# ATX_Power_Supply.net
KiCad netlist of a schematic drawn in EAGLE
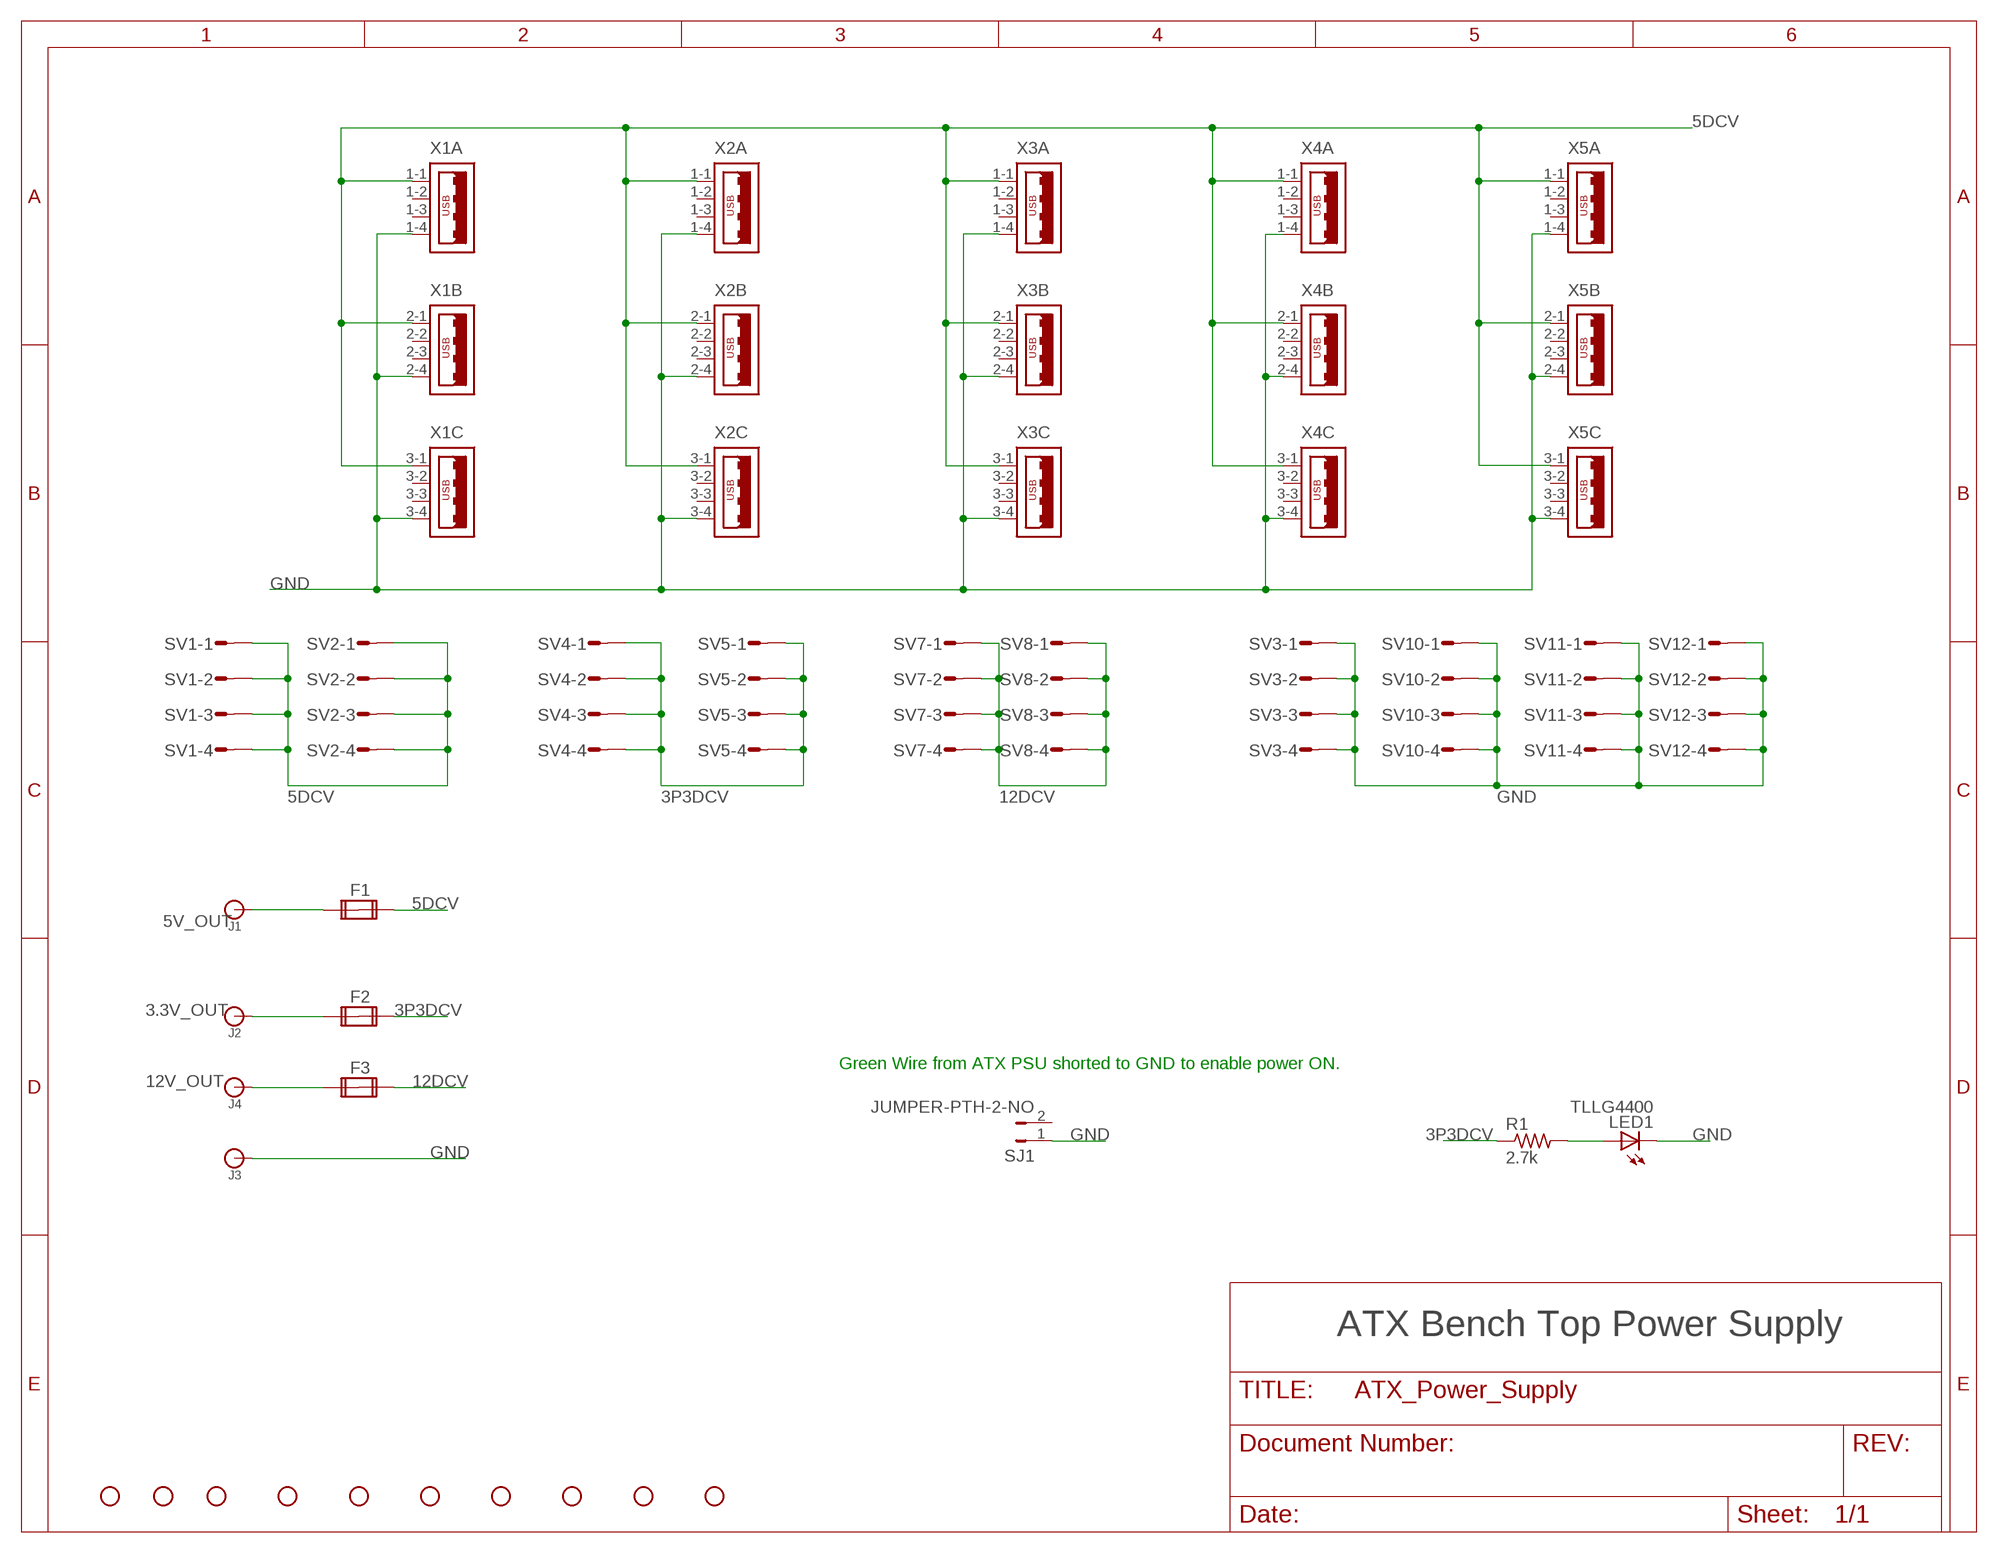
[diagram p0: schematic, sheet 1]

(export (version "E")
  (design (tool "Eeschema 10.0.6"))
  (components
    (comp (ref "F1")
      (value "FUSE2P")
      (footprint "eagle-import:FUSE1")
      (libsource (lib "eagle-import") (part "FUSE2P"))
    )
    (comp (ref "F2")
      (value "FUSE2P")
      (footprint "eagle-import:FUSE1")
      (libsource (lib "eagle-import") (part "FUSE2P"))
    )
    (comp (ref "F3")
      (value "FUSE2P")
      (footprint "eagle-import:FUSE1")
      (libsource (lib "eagle-import") (part "FUSE2P"))
    )
    (comp (ref "J1")
      (value "BANANA_CONN")
      (footprint "eagle-import:BANANA_CONN")
      (libsource (lib "eagle-import") (part "BANANA_CONN"))
    )
    (comp (ref "J2")
      (value "BANANA_CONN")
      (footprint "eagle-import:BANANA_CONN")
      (libsource (lib "eagle-import") (part "BANANA_CONN"))
    )
    (comp (ref "J3")
      (value "BANANA_CONN")
      (footprint "eagle-import:BANANA_CONN")
      (libsource (lib "eagle-import") (part "BANANA_CONN"))
    )
    (comp (ref "J4")
      (value "BANANA_CONN")
      (footprint "eagle-import:BANANA_CONN")
      (libsource (lib "eagle-import") (part "BANANA_CONN"))
    )
    (comp (ref "LED1")
      (value "TLLG4400")
      (footprint "eagle-import:LED3MM")
      (fields (field (name "MF") "VISHAY SEMICONDUCTOR"))
      (libsource (lib "eagle-import") (part "TLLG4400"))
    )
    (comp (ref "R1")
      (value "2.7k")
      (footprint "eagle-import:0204_5")
      (libsource (lib "eagle-import") (part "R-US_0204/5"))
    )
    (comp (ref "SJ1")
      (value "JUMPER-PTH-2-NO")
      (footprint "eagle-import:PTH-JUMPER-2-NO_NO_SILK")
      (libsource (lib "eagle-import") (part "JUMPER-PTH-2-NO"))
    )
    (comp (ref "STANDOFF1")
      (value "STAND-OFF")
      (footprint "eagle-import:STAND-OFF")
      (libsource (lib "eagle-import") (part "STAND-OFF"))
    )
    (comp (ref "STANDOFF2")
      (value "STAND-OFF")
      (footprint "eagle-import:STAND-OFF")
      (libsource (lib "eagle-import") (part "STAND-OFF"))
    )
    (comp (ref "STANDOFF3")
      (value "STAND-OFF")
      (footprint "eagle-import:STAND-OFF")
      (libsource (lib "eagle-import") (part "STAND-OFF"))
    )
    (comp (ref "STANDOFF4")
      (value "STAND-OFF")
      (footprint "eagle-import:STAND-OFF")
      (libsource (lib "eagle-import") (part "STAND-OFF"))
    )
    (comp (ref "STANDOFF5")
      (value "STAND-OFF")
      (footprint "eagle-import:STAND-OFF")
      (libsource (lib "eagle-import") (part "STAND-OFF"))
    )
    (comp (ref "STANDOFF6")
      (value "STAND-OFF")
      (footprint "eagle-import:STAND-OFF")
      (libsource (lib "eagle-import") (part "STAND-OFF"))
    )
    (comp (ref "STANDOFF7")
      (value "STAND-OFF")
      (footprint "eagle-import:STAND-OFF")
      (libsource (lib "eagle-import") (part "STAND-OFF"))
    )
    (comp (ref "STANDOFF8")
      (value "STAND-OFF")
      (footprint "eagle-import:STAND-OFF")
      (libsource (lib "eagle-import") (part "STAND-OFF"))
    )
    (comp (ref "STANDOFF9")
      (value "STAND-OFF")
      (footprint "eagle-import:STAND-OFF")
      (libsource (lib "eagle-import") (part "STAND-OFF"))
    )
    (comp (ref "STANDOFF10")
      (value "STAND-OFF")
      (footprint "eagle-import:STAND-OFF")
      (libsource (lib "eagle-import") (part "STAND-OFF"))
    )
    (comp (ref "SV1")
      (value "MT6-4")
      (footprint "eagle-import:MT6-4")
      (libsource (lib "eagle-import") (part "MT6-4"))
    )
    (comp (ref "SV2")
      (value "MT6-4")
      (footprint "eagle-import:MT6-4")
      (libsource (lib "eagle-import") (part "MT6-4"))
    )
    (comp (ref "SV3")
      (value "MT6-4")
      (footprint "eagle-import:MT6-4")
      (libsource (lib "eagle-import") (part "MT6-4"))
    )
    (comp (ref "SV4")
      (value "MT6-4")
      (footprint "eagle-import:MT6-4")
      (libsource (lib "eagle-import") (part "MT6-4"))
    )
    (comp (ref "SV5")
      (value "MT6-4")
      (footprint "eagle-import:MT6-4")
      (libsource (lib "eagle-import") (part "MT6-4"))
    )
    (comp (ref "SV7")
      (value "MT6-4")
      (footprint "eagle-import:MT6-4")
      (libsource (lib "eagle-import") (part "MT6-4"))
    )
    (comp (ref "SV8")
      (value "MT6-4")
      (footprint "eagle-import:MT6-4")
      (libsource (lib "eagle-import") (part "MT6-4"))
    )
    (comp (ref "SV10")
      (value "MT6-4")
      (footprint "eagle-import:MT6-4")
      (libsource (lib "eagle-import") (part "MT6-4"))
    )
    (comp (ref "SV11")
      (value "MT6-4")
      (footprint "eagle-import:MT6-4")
      (libsource (lib "eagle-import") (part "MT6-4"))
    )
    (comp (ref "SV12")
      (value "MT6-4")
      (footprint "eagle-import:MT6-4")
      (libsource (lib "eagle-import") (part "MT6-4"))
    )
    (comp (ref "X1")
      (value "USB_3PSHIELD-85-32003-00X-1")
      (footprint "eagle-import:85-32003-00X-1")
      (libsource (lib "eagle-import") (part "USB_3PSHIELD-85-32003-00X-1"))
    )
    (comp (ref "X2")
      (value "USB_3PSHIELD-85-32003-00X-1")
      (footprint "eagle-import:85-32003-00X-1")
      (libsource (lib "eagle-import") (part "USB_3PSHIELD-85-32003-00X-1"))
    )
    (comp (ref "X3")
      (value "USB_3PSHIELD-85-32003-00X-1")
      (footprint "eagle-import:85-32003-00X-1")
      (libsource (lib "eagle-import") (part "USB_3PSHIELD-85-32003-00X-1"))
    )
    (comp (ref "X4")
      (value "USB_3PSHIELD-85-32003-00X-1")
      (footprint "eagle-import:85-32003-00X-1")
      (libsource (lib "eagle-import") (part "USB_3PSHIELD-85-32003-00X-1"))
    )
    (comp (ref "X5")
      (value "USB_3PSHIELD-85-32003-00X-1")
      (footprint "eagle-import:85-32003-00X-1")
      (libsource (lib "eagle-import") (part "USB_3PSHIELD-85-32003-00X-1"))
    )
  )
  (nets
    (net (code "1") (name "/3.3V_OUT") (class "Default")
      (node (ref "F2") (pin "1A") (pinfunction "1A_1A") (pintype "passive"))
      (node (ref "J2") (pin "P$1") (pinfunction "1_P$1") (pintype "passive"))
    )
    (net (code "2") (name "/3P3DCV") (class "Default")
      (node (ref "F2") (pin "2A") (pinfunction "2A_2A") (pintype "passive"))
      (node (ref "R1") (pin "1") (pinfunction "1_1") (pintype "passive"))
      (node (ref "SV4") (pin "1") (pinfunction "S_1") (pintype "passive"))
      (node (ref "SV4") (pin "2") (pinfunction "S_2") (pintype "passive"))
      (node (ref "SV4") (pin "3") (pinfunction "S_3") (pintype "passive"))
      (node (ref "SV4") (pin "4") (pinfunction "S_4") (pintype "passive"))
      (node (ref "SV5") (pin "1") (pinfunction "S_1") (pintype "passive"))
      (node (ref "SV5") (pin "2") (pinfunction "S_2") (pintype "passive"))
      (node (ref "SV5") (pin "3") (pinfunction "S_3") (pintype "passive"))
      (node (ref "SV5") (pin "4") (pinfunction "S_4") (pintype "passive"))
    )
    (net (code "3") (name "/5DCV") (class "Default")
      (node (ref "F1") (pin "2A") (pinfunction "2A_2A") (pintype "passive"))
      (node (ref "SV1") (pin "1") (pinfunction "S_1") (pintype "passive"))
      (node (ref "SV1") (pin "2") (pinfunction "S_2") (pintype "passive"))
      (node (ref "SV1") (pin "3") (pinfunction "S_3") (pintype "passive"))
      (node (ref "SV1") (pin "4") (pinfunction "S_4") (pintype "passive"))
      (node (ref "SV2") (pin "1") (pinfunction "S_1") (pintype "passive"))
      (node (ref "SV2") (pin "2") (pinfunction "S_2") (pintype "passive"))
      (node (ref "SV2") (pin "3") (pinfunction "S_3") (pintype "passive"))
      (node (ref "SV2") (pin "4") (pinfunction "S_4") (pintype "passive"))
      (node (ref "X1") (pin "1-1") (pinfunction "1_1-1") (pintype "passive"))
      (node (ref "X1") (pin "2-1") (pinfunction "1_2-1") (pintype "passive"))
      (node (ref "X1") (pin "3-1") (pinfunction "1_3-1") (pintype "passive"))
      (node (ref "X2") (pin "1-1") (pinfunction "1_1-1") (pintype "passive"))
      (node (ref "X2") (pin "2-1") (pinfunction "1_2-1") (pintype "passive"))
      (node (ref "X2") (pin "3-1") (pinfunction "1_3-1") (pintype "passive"))
      (node (ref "X3") (pin "1-1") (pinfunction "1_1-1") (pintype "passive"))
      (node (ref "X3") (pin "2-1") (pinfunction "1_2-1") (pintype "passive"))
      (node (ref "X3") (pin "3-1") (pinfunction "1_3-1") (pintype "passive"))
      (node (ref "X4") (pin "1-1") (pinfunction "1_1-1") (pintype "passive"))
      (node (ref "X4") (pin "2-1") (pinfunction "1_2-1") (pintype "passive"))
      (node (ref "X4") (pin "3-1") (pinfunction "1_3-1") (pintype "passive"))
      (node (ref "X5") (pin "1-1") (pinfunction "1_1-1") (pintype "passive"))
      (node (ref "X5") (pin "2-1") (pinfunction "1_2-1") (pintype "passive"))
      (node (ref "X5") (pin "3-1") (pinfunction "1_3-1") (pintype "passive"))
    )
    (net (code "4") (name "/5V_OUT") (class "Default")
      (node (ref "F1") (pin "1A") (pinfunction "1A_1A") (pintype "passive"))
      (node (ref "J1") (pin "P$1") (pinfunction "1_P$1") (pintype "passive"))
    )
    (net (code "5") (name "/12DCV") (class "Default")
      (node (ref "F3") (pin "2A") (pinfunction "2A_2A") (pintype "passive"))
      (node (ref "SV7") (pin "1") (pinfunction "S_1") (pintype "passive"))
      (node (ref "SV7") (pin "2") (pinfunction "S_2") (pintype "passive"))
      (node (ref "SV7") (pin "3") (pinfunction "S_3") (pintype "passive"))
      (node (ref "SV7") (pin "4") (pinfunction "S_4") (pintype "passive"))
      (node (ref "SV8") (pin "1") (pinfunction "S_1") (pintype "passive"))
      (node (ref "SV8") (pin "2") (pinfunction "S_2") (pintype "passive"))
      (node (ref "SV8") (pin "3") (pinfunction "S_3") (pintype "passive"))
      (node (ref "SV8") (pin "4") (pinfunction "S_4") (pintype "passive"))
    )
    (net (code "6") (name "/12V_OUT") (class "Default")
      (node (ref "F3") (pin "1A") (pinfunction "1A_1A") (pintype "passive"))
      (node (ref "J4") (pin "P$1") (pinfunction "1_P$1") (pintype "passive"))
    )
    (net (code "7") (name "/GND") (class "Default")
      (node (ref "J3") (pin "P$1") (pinfunction "1_P$1") (pintype "passive"))
      (node (ref "LED1") (pin "K") (pinfunction "C_K") (pintype "passive"))
      (node (ref "SJ1") (pin "1") (pinfunction "1_1") (pintype "passive"))
      (node (ref "SV10") (pin "1") (pinfunction "S_1") (pintype "passive"))
      (node (ref "SV10") (pin "2") (pinfunction "S_2") (pintype "passive"))
      (node (ref "SV10") (pin "3") (pinfunction "S_3") (pintype "passive"))
      (node (ref "SV10") (pin "4") (pinfunction "S_4") (pintype "passive"))
      (node (ref "SV11") (pin "1") (pinfunction "S_1") (pintype "passive"))
      (node (ref "SV11") (pin "2") (pinfunction "S_2") (pintype "passive"))
      (node (ref "SV11") (pin "3") (pinfunction "S_3") (pintype "passive"))
      (node (ref "SV11") (pin "4") (pinfunction "S_4") (pintype "passive"))
      (node (ref "SV12") (pin "1") (pinfunction "S_1") (pintype "passive"))
      (node (ref "SV12") (pin "2") (pinfunction "S_2") (pintype "passive"))
      (node (ref "SV12") (pin "3") (pinfunction "S_3") (pintype "passive"))
      (node (ref "SV12") (pin "4") (pinfunction "S_4") (pintype "passive"))
      (node (ref "SV3") (pin "1") (pinfunction "S_1") (pintype "passive"))
      (node (ref "SV3") (pin "2") (pinfunction "S_2") (pintype "passive"))
      (node (ref "SV3") (pin "3") (pinfunction "S_3") (pintype "passive"))
      (node (ref "SV3") (pin "4") (pinfunction "S_4") (pintype "passive"))
      (node (ref "X1") (pin "1-4") (pinfunction "4_1-4") (pintype "passive"))
      (node (ref "X1") (pin "2-4") (pinfunction "4_2-4") (pintype "passive"))
      (node (ref "X1") (pin "3-4") (pinfunction "4_3-4") (pintype "passive"))
      (node (ref "X2") (pin "1-4") (pinfunction "4_1-4") (pintype "passive"))
      (node (ref "X2") (pin "2-4") (pinfunction "4_2-4") (pintype "passive"))
      (node (ref "X2") (pin "3-4") (pinfunction "4_3-4") (pintype "passive"))
      (node (ref "X3") (pin "1-4") (pinfunction "4_1-4") (pintype "passive"))
      (node (ref "X3") (pin "2-4") (pinfunction "4_2-4") (pintype "passive"))
      (node (ref "X3") (pin "3-4") (pinfunction "4_3-4") (pintype "passive"))
      (node (ref "X4") (pin "1-4") (pinfunction "4_1-4") (pintype "passive"))
      (node (ref "X4") (pin "2-4") (pinfunction "4_2-4") (pintype "passive"))
      (node (ref "X4") (pin "3-4") (pinfunction "4_3-4") (pintype "passive"))
      (node (ref "X5") (pin "1-4") (pinfunction "4_1-4") (pintype "passive"))
      (node (ref "X5") (pin "2-4") (pinfunction "4_2-4") (pintype "passive"))
      (node (ref "X5") (pin "3-4") (pinfunction "4_3-4") (pintype "passive"))
    )
    (net (code "8") (name "Net-(LED1-PadA)") (class "Default")
      (node (ref "LED1") (pin "A") (pinfunction "A_A") (pintype "passive"))
      (node (ref "R1") (pin "2") (pinfunction "2_2") (pintype "passive"))
    )
    (net (code "9") (name "unconnected-(F1-Pad1B)") (class "Default")
      (node (ref "F1") (pin "1B") (pinfunction "1B_1B") (pintype "passive"))
    )
    (net (code "10") (name "unconnected-(F1-Pad2B)") (class "Default")
      (node (ref "F1") (pin "2B") (pinfunction "2B_2B") (pintype "passive"))
    )
    (net (code "11") (name "unconnected-(F2-Pad1B)") (class "Default")
      (node (ref "F2") (pin "1B") (pinfunction "1B_1B") (pintype "passive"))
    )
    (net (code "12") (name "unconnected-(F2-Pad2B)") (class "Default")
      (node (ref "F2") (pin "2B") (pinfunction "2B_2B") (pintype "passive"))
    )
    (net (code "13") (name "unconnected-(F3-Pad1B)") (class "Default")
      (node (ref "F3") (pin "1B") (pinfunction "1B_1B") (pintype "passive"))
    )
    (net (code "14") (name "unconnected-(F3-Pad2B)") (class "Default")
      (node (ref "F3") (pin "2B") (pinfunction "2B_2B") (pintype "passive"))
    )
    (net (code "15") (name "unconnected-(SJ1-Pad2)") (class "Default")
      (node (ref "SJ1") (pin "2") (pinfunction "2_2") (pintype "passive"))
    )
    (net (code "16") (name "unconnected-(X1A-2-Pad1-2)") (class "Default")
      (node (ref "X1") (pin "1-2") (pinfunction "2_1-2") (pintype "passive"))
    )
    (net (code "17") (name "unconnected-(X1A-3-Pad1-3)") (class "Default")
      (node (ref "X1") (pin "1-3") (pinfunction "3_1-3") (pintype "passive"))
    )
    (net (code "18") (name "unconnected-(X1B-2-Pad2-2)") (class "Default")
      (node (ref "X1") (pin "2-2") (pinfunction "2_2-2") (pintype "passive"))
    )
    (net (code "19") (name "unconnected-(X1B-3-Pad2-3)") (class "Default")
      (node (ref "X1") (pin "2-3") (pinfunction "3_2-3") (pintype "passive"))
    )
    (net (code "20") (name "unconnected-(X1C-2-Pad3-2)") (class "Default")
      (node (ref "X1") (pin "3-2") (pinfunction "2_3-2") (pintype "passive"))
    )
    (net (code "21") (name "unconnected-(X1C-3-Pad3-3)") (class "Default")
      (node (ref "X1") (pin "3-3") (pinfunction "3_3-3") (pintype "passive"))
    )
    (net (code "22") (name "unconnected-(X2A-2-Pad1-2)") (class "Default")
      (node (ref "X2") (pin "1-2") (pinfunction "2_1-2") (pintype "passive"))
    )
    (net (code "23") (name "unconnected-(X2A-3-Pad1-3)") (class "Default")
      (node (ref "X2") (pin "1-3") (pinfunction "3_1-3") (pintype "passive"))
    )
    (net (code "24") (name "unconnected-(X2B-2-Pad2-2)") (class "Default")
      (node (ref "X2") (pin "2-2") (pinfunction "2_2-2") (pintype "passive"))
    )
    (net (code "25") (name "unconnected-(X2B-3-Pad2-3)") (class "Default")
      (node (ref "X2") (pin "2-3") (pinfunction "3_2-3") (pintype "passive"))
    )
    (net (code "26") (name "unconnected-(X2C-2-Pad3-2)") (class "Default")
      (node (ref "X2") (pin "3-2") (pinfunction "2_3-2") (pintype "passive"))
    )
    (net (code "27") (name "unconnected-(X2C-3-Pad3-3)") (class "Default")
      (node (ref "X2") (pin "3-3") (pinfunction "3_3-3") (pintype "passive"))
    )
    (net (code "28") (name "unconnected-(X3A-2-Pad1-2)") (class "Default")
      (node (ref "X3") (pin "1-2") (pinfunction "2_1-2") (pintype "passive"))
    )
    (net (code "29") (name "unconnected-(X3A-3-Pad1-3)") (class "Default")
      (node (ref "X3") (pin "1-3") (pinfunction "3_1-3") (pintype "passive"))
    )
    (net (code "30") (name "unconnected-(X3B-2-Pad2-2)") (class "Default")
      (node (ref "X3") (pin "2-2") (pinfunction "2_2-2") (pintype "passive"))
    )
    (net (code "31") (name "unconnected-(X3B-3-Pad2-3)") (class "Default")
      (node (ref "X3") (pin "2-3") (pinfunction "3_2-3") (pintype "passive"))
    )
    (net (code "32") (name "unconnected-(X3C-2-Pad3-2)") (class "Default")
      (node (ref "X3") (pin "3-2") (pinfunction "2_3-2") (pintype "passive"))
    )
    (net (code "33") (name "unconnected-(X3C-3-Pad3-3)") (class "Default")
      (node (ref "X3") (pin "3-3") (pinfunction "3_3-3") (pintype "passive"))
    )
    (net (code "34") (name "unconnected-(X4A-2-Pad1-2)") (class "Default")
      (node (ref "X4") (pin "1-2") (pinfunction "2_1-2") (pintype "passive"))
    )
    (net (code "35") (name "unconnected-(X4A-3-Pad1-3)") (class "Default")
      (node (ref "X4") (pin "1-3") (pinfunction "3_1-3") (pintype "passive"))
    )
    (net (code "36") (name "unconnected-(X4B-2-Pad2-2)") (class "Default")
      (node (ref "X4") (pin "2-2") (pinfunction "2_2-2") (pintype "passive"))
    )
    (net (code "37") (name "unconnected-(X4B-3-Pad2-3)") (class "Default")
      (node (ref "X4") (pin "2-3") (pinfunction "3_2-3") (pintype "passive"))
    )
    (net (code "38") (name "unconnected-(X4C-2-Pad3-2)") (class "Default")
      (node (ref "X4") (pin "3-2") (pinfunction "2_3-2") (pintype "passive"))
    )
    (net (code "39") (name "unconnected-(X4C-3-Pad3-3)") (class "Default")
      (node (ref "X4") (pin "3-3") (pinfunction "3_3-3") (pintype "passive"))
    )
    (net (code "40") (name "unconnected-(X5A-2-Pad1-2)") (class "Default")
      (node (ref "X5") (pin "1-2") (pinfunction "2_1-2") (pintype "passive"))
    )
    (net (code "41") (name "unconnected-(X5A-3-Pad1-3)") (class "Default")
      (node (ref "X5") (pin "1-3") (pinfunction "3_1-3") (pintype "passive"))
    )
    (net (code "42") (name "unconnected-(X5B-2-Pad2-2)") (class "Default")
      (node (ref "X5") (pin "2-2") (pinfunction "2_2-2") (pintype "passive"))
    )
    (net (code "43") (name "unconnected-(X5B-3-Pad2-3)") (class "Default")
      (node (ref "X5") (pin "2-3") (pinfunction "3_2-3") (pintype "passive"))
    )
    (net (code "44") (name "unconnected-(X5C-2-Pad3-2)") (class "Default")
      (node (ref "X5") (pin "3-2") (pinfunction "2_3-2") (pintype "passive"))
    )
    (net (code "45") (name "unconnected-(X5C-3-Pad3-3)") (class "Default")
      (node (ref "X5") (pin "3-3") (pinfunction "3_3-3") (pintype "passive"))
    )
  )
)
